# PCB_m5_Sheet.net
KiCad netlist of a schematic drawn in Altium Designer
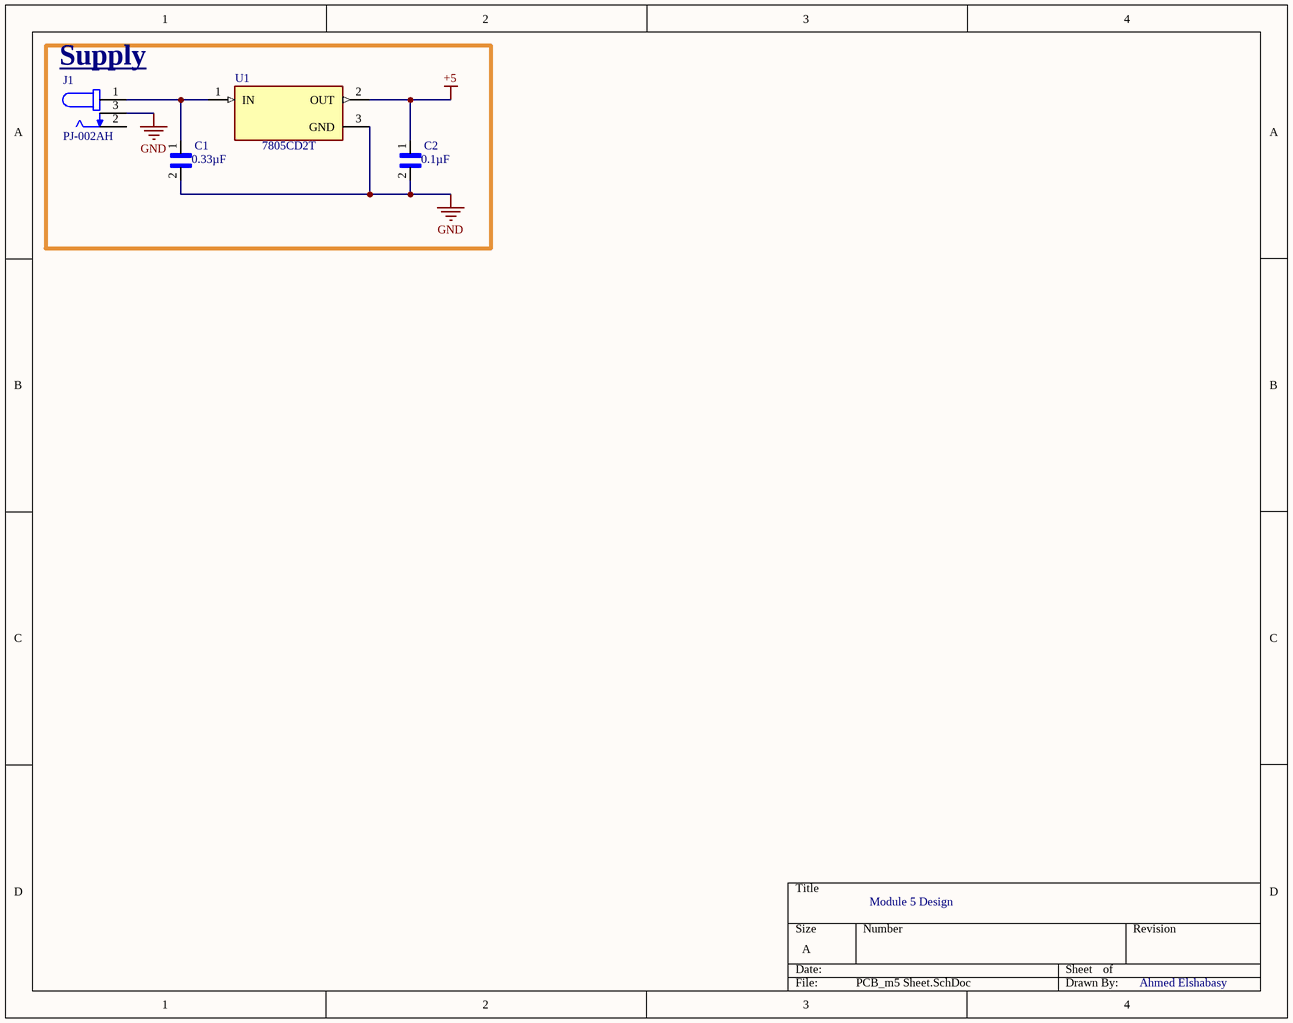
[diagram p0: PCB_m5 Sheet.SchDoc]

(export (version "E")
  (design (tool "Eeschema 10.0.6"))
  (components
    (comp (ref "C1")
      (value "0.33µF")
      (footprint "CAPC3216X190N")
      (description "SMD Multilayer Ceramic Capacitor, GRM Series, 220 F, 20%, X5R, 6.3 V, 1206 [3216 Metric]")
      (fields (field (name "DIGI-KEY_PART_NUMBER") "490-13970-1-ND") (field (name "MP") "GRM31CR60J227ME11L"))
      (libsource (lib "GRM31CR60J227ME11L") (part "GRM31CR60J227ME11L"))
    )
    (comp (ref "C2")
      (value "0.1µF")
      (footprint "CAPC3216X190N")
      (description "SMD Multilayer Ceramic Capacitor, GRM Series, 220 F, 20%, X5R, 6.3 V, 1206 [3216 Metric]")
      (fields (field (name "DIGI-KEY_PART_NUMBER") "490-13970-1-ND") (field (name "MP") "GRM31CR60J227ME11L"))
      (libsource (lib "GRM31CR60J227ME11L") (part "GRM31CR60J227ME11L"))
    )
    (comp (ref "J1")
      (value "PJ-002AH")
      (footprint "CUI_PJ-002AH")
      (description "2.0 x 6.5 mm, 5.0 A, Horizontal, Through Hole, Dc Power Jack Connector")
      (fields (field (name "MF") "CUI Devices"))
      (libsource (lib "PJ-002AH") (part "PJ-002AH"))
    )
    (comp (ref "U1")
      (value "7805CD2T")
      (footprint "TO254P1542X460-3N")
      (description "Linear Voltage Regulator IC Positive Fixed 1 Output 1.5A D2PAK")
      (fields (field (name "MF") "STMicroelectronics"))
      (libsource (lib "7805CD2T") (part "7805CD2T"))
    )
  )
  (nets
    (net (code "1") (name "+5") (class "Default")
      (node (ref "C2") (pin "1") (pinfunction "1_1") (pintype "passive"))
      (node (ref "U1") (pin "2") (pinfunction "OUT_2") (pintype "output"))
    )
    (net (code "2") (name "GND") (class "Default")
      (node (ref "C1") (pin "2") (pinfunction "2_2") (pintype "passive"))
      (node (ref "C2") (pin "2") (pinfunction "2_2") (pintype "passive"))
      (node (ref "J1") (pin "3") (pinfunction "3_3") (pintype "passive"))
      (node (ref "U1") (pin "3") (pinfunction "GND_3") (pintype "power_in"))
    )
    (net (code "3") (name "Net-(U1-IN)") (class "Default")
      (node (ref "C1") (pin "1") (pinfunction "1_1") (pintype "passive"))
      (node (ref "J1") (pin "1") (pinfunction "1_1") (pintype "passive"))
      (node (ref "U1") (pin "1") (pinfunction "IN_1") (pintype "input"))
    )
    (net (code "4") (name "unconnected-(J1-Pad2)") (class "Default")
      (node (ref "J1") (pin "2") (pinfunction "2_2") (pintype "passive"))
    )
  )
)
